# eeZeeProp.net
KiCad netlist of a schematic drawn in EAGLE
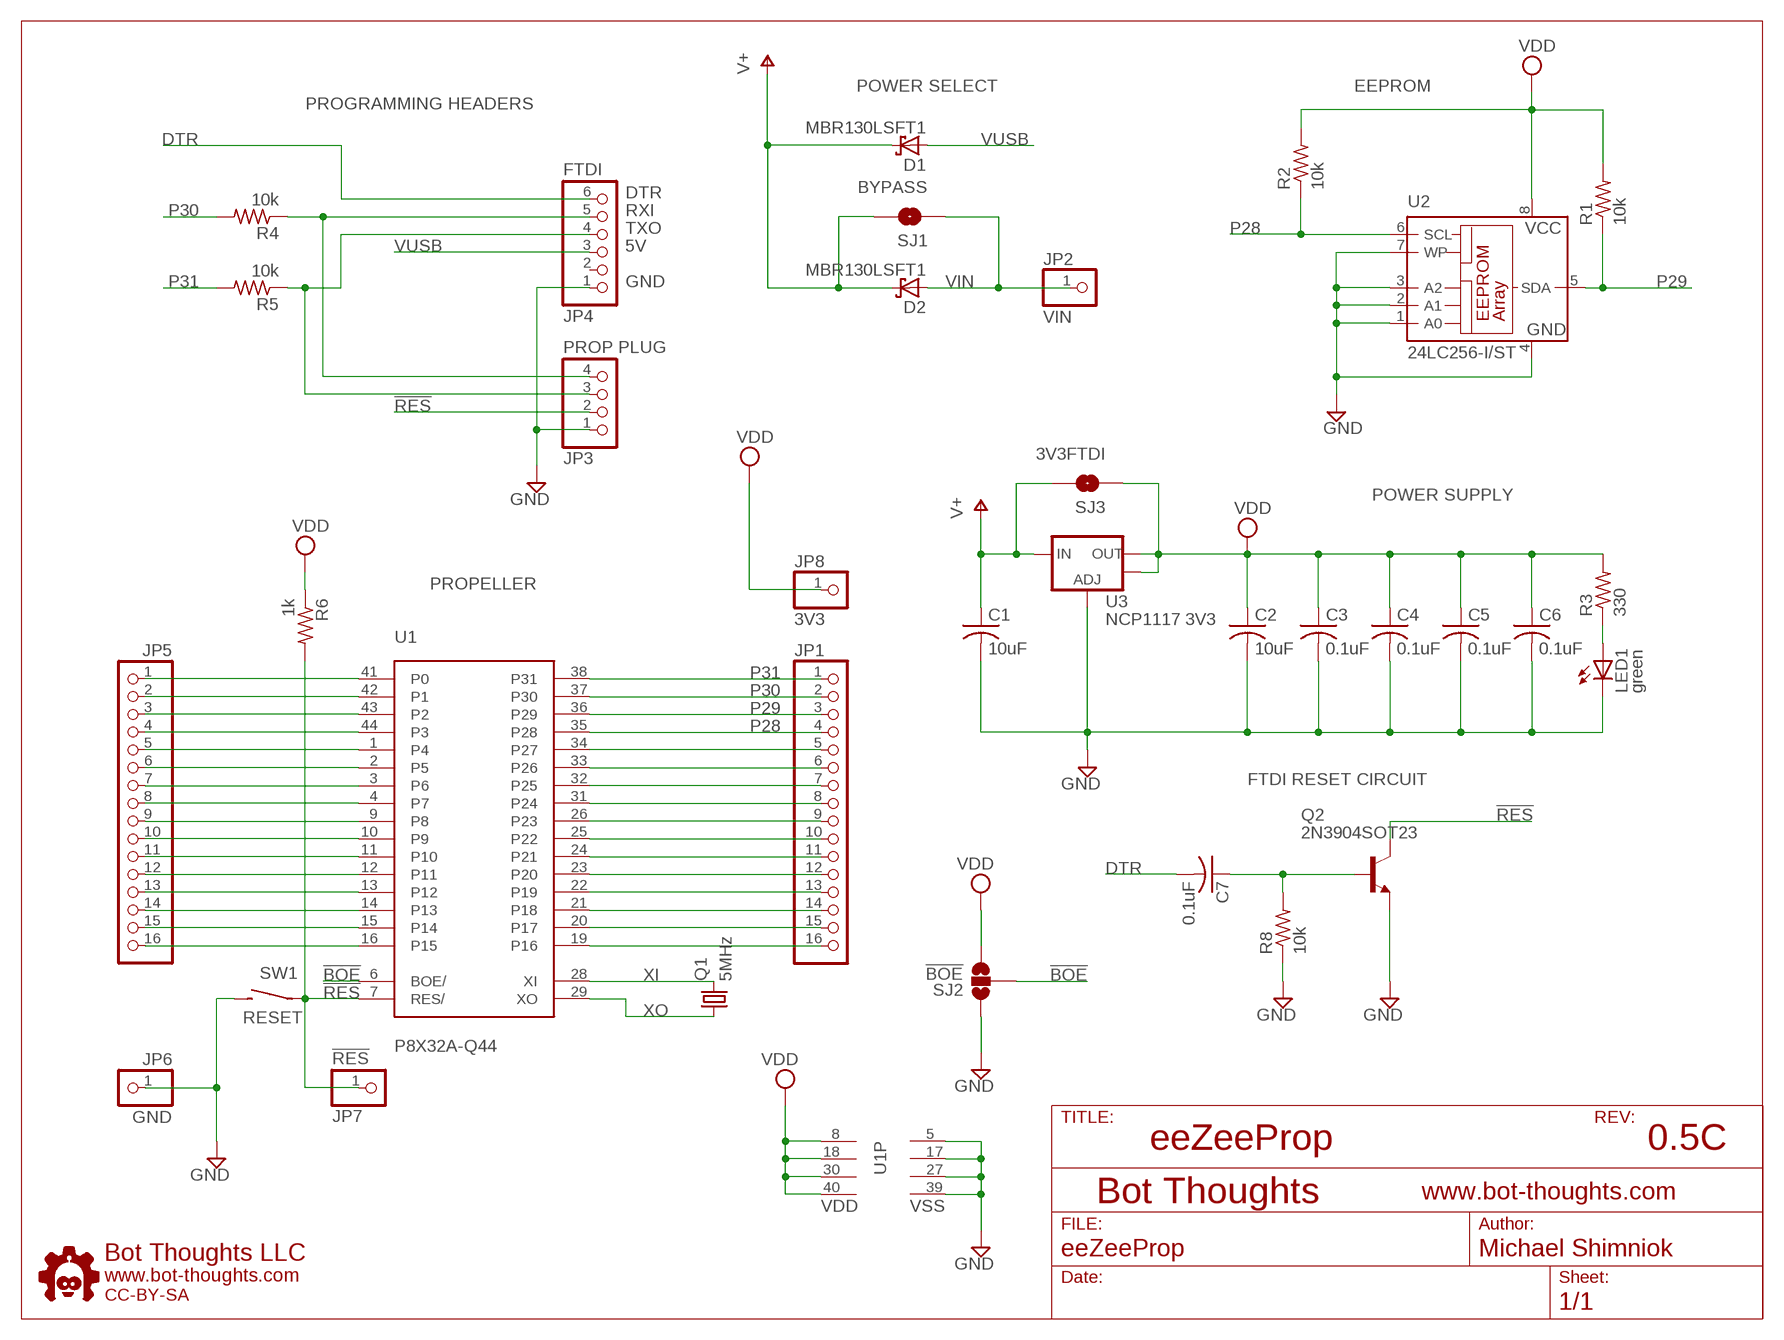
[diagram p0: schematic, sheet 1]

(export (version "E")
  (design (tool "Eeschema 10.0.6"))
  (components
    (comp (ref "C1")
      (value "10uF")
      (footprint "eagle-import:C1206")
      (fields (field (name "PARTNO") "T491A106M006AT"))
      (libsource (lib "eagle-import") (part "C-USC1206"))
    )
    (comp (ref "C2")
      (value "10uF")
      (footprint "eagle-import:C1206")
      (fields (field (name "PARTNO") "T491A106M006AT"))
      (libsource (lib "eagle-import") (part "C-USC1206"))
    )
    (comp (ref "C3")
      (value "0.1uF")
      (footprint "eagle-import:C0603")
      (fields (field (name "PARTNO") "0603YC104KAT2A"))
      (libsource (lib "eagle-import") (part "C-USC0603"))
    )
    (comp (ref "C4")
      (value "0.1uF")
      (footprint "eagle-import:C0603")
      (fields (field (name "PARTNO") "0603YC104KAT2A"))
      (libsource (lib "eagle-import") (part "C-USC0603"))
    )
    (comp (ref "C5")
      (value "0.1uF")
      (footprint "eagle-import:C0603")
      (fields (field (name "PARTNO") "0603YC104KAT2A"))
      (libsource (lib "eagle-import") (part "C-USC0603"))
    )
    (comp (ref "C6")
      (value "0.1uF")
      (footprint "eagle-import:C0603")
      (fields (field (name "PARTNO") "0603YC104KAT2A"))
      (libsource (lib "eagle-import") (part "C-USC0603"))
    )
    (comp (ref "C7")
      (value "0.1uF")
      (footprint "eagle-import:C0603")
      (fields (field (name "PARTNO") "0603YC104KAT2A"))
      (libsource (lib "eagle-import") (part "C-USC0603"))
    )
    (comp (ref "D1")
      (value "MBR130LSFT1")
      (footprint "eagle-import:SOD123FL")
      (fields (field (name "PARTNO") "MBR130LSFT1G"))
      (libsource (lib "eagle-import") (part "SCHOTTKY-DIODE-MBR130LSFT1"))
    )
    (comp (ref "D2")
      (value "MBR130LSFT1")
      (footprint "eagle-import:SOD123FL")
      (fields (field (name "PARTNO") "MBR130LSFT1G"))
      (libsource (lib "eagle-import") (part "SCHOTTKY-DIODE-MBR130LSFT1"))
    )
    (comp (ref "JP1")
      (value "PINHD-1X16_2.54-S")
      (footprint "eagle-import:1X16-S")
      (libsource (lib "eagle-import") (part "PINHD-1X16_2.54-S"))
    )
    (comp (ref "JP2")
      (value "VIN")
      (footprint "eagle-import:1X01")
      (libsource (lib "eagle-import") (part "PINHD-1X01_2.54"))
    )
    (comp (ref "JP3")
      (value "PROP PLUG")
      (footprint "eagle-import:1X04-S")
      (libsource (lib "eagle-import") (part "PINHD-1X04_2.54-S"))
    )
    (comp (ref "JP4")
      (value "FTDI")
      (footprint "eagle-import:1X06-S")
      (fields (field (name "PARTNO") "2211S-06G"))
      (libsource (lib "eagle-import") (part "PINHD-1X06_2.54-S"))
    )
    (comp (ref "JP5")
      (value "PINHD-1X16_2.54-S")
      (footprint "eagle-import:1X16-S")
      (libsource (lib "eagle-import") (part "PINHD-1X16_2.54-S"))
    )
    (comp (ref "JP6")
      (value "GND")
      (footprint "eagle-import:1X01")
      (libsource (lib "eagle-import") (part "PINHD-1X01_2.54"))
    )
    (comp (ref "JP7")
      (value "!RES")
      (footprint "eagle-import:1X01")
      (libsource (lib "eagle-import") (part "PINHD-1X01_2.54"))
    )
    (comp (ref "JP8")
      (value "3V3")
      (footprint "eagle-import:1X01")
      (libsource (lib "eagle-import") (part "PINHD-1X01_2.54"))
    )
    (comp (ref "LED1")
      (value "green")
      (footprint "eagle-import:CHIPLED_1206")
      (fields (field (name "PARTNO") "LG N971-KN-1"))
      (libsource (lib "eagle-import") (part "LEDCHIPLED_1206"))
    )
    (comp (ref "Q1")
      (value "5MHz")
      (footprint "eagle-import:HC49U-V")
      (fields (field (name "OC_FARNELL") "1666969") (field (name "PARTNO") "HC49US-5.000MABJ-UB"))
      (libsource (lib "eagle-import") (part "CRYSTALHC49U-V"))
    )
    (comp (ref "Q2")
      (value "2N3904SOT23")
      (footprint "eagle-import:SOT-23")
      (fields (field (name "PARTNO") "MMBT3904LT3G"))
      (libsource (lib "eagle-import") (part "2N3904SOT23"))
    )
    (comp (ref "R1")
      (value "10k")
      (footprint "eagle-import:R0603")
      (fields (field (name "PARTNO") "ERJ-3GEYJ103V"))
      (libsource (lib "eagle-import") (part "R-US_R0603"))
    )
    (comp (ref "R2")
      (value "10k")
      (footprint "eagle-import:R0603")
      (fields (field (name "PARTNO") "ERJ-3GEYJ103V"))
      (libsource (lib "eagle-import") (part "R-US_R0603"))
    )
    (comp (ref "R3")
      (value "330")
      (footprint "eagle-import:R0603")
      (fields (field (name "PARTNO") "ERJ-3GEYJ331V"))
      (libsource (lib "eagle-import") (part "R-US_R0603"))
    )
    (comp (ref "R4")
      (value "10k")
      (footprint "eagle-import:R0603")
      (fields (field (name "PARTNO") "RC0603JR-071KL"))
      (libsource (lib "eagle-import") (part "R-US_R0603"))
    )
    (comp (ref "R5")
      (value "10k")
      (footprint "eagle-import:R0603")
      (fields (field (name "PARTNO") "RC0603JR-071KL"))
      (libsource (lib "eagle-import") (part "R-US_R0603"))
    )
    (comp (ref "R6")
      (value "1k")
      (footprint "eagle-import:R0603")
      (fields (field (name "PARTNO") "RC0603JR-071KL"))
      (libsource (lib "eagle-import") (part "R-US_R0603"))
    )
    (comp (ref "R8")
      (value "10k")
      (footprint "eagle-import:R0603")
      (fields (field (name "PARTNO") "ERJ-3GEYJ103V"))
      (libsource (lib "eagle-import") (part "R-US_R0603"))
    )
    (comp (ref "SJ1")
      (value "BYPASS")
      (footprint "eagle-import:SJ_2S-NO")
      (libsource (lib "eagle-import") (part "SOLDERJUMPERNO"))
    )
    (comp (ref "SJ2")
      (value "!BOE")
      (footprint "eagle-import:SJ_3")
      (libsource (lib "eagle-import") (part "SOLDERJUMPER_2WAYS"))
    )
    (comp (ref "SJ3")
      (value "3V3FTDI")
      (footprint "eagle-import:SJ_2S-NO")
      (libsource (lib "eagle-import") (part "SOLDERJUMPERNO"))
    )
    (comp (ref "SW1")
      (value "RESET")
      (footprint "eagle-import:6MMTACTILE_RECT")
      (fields (field (name "PARTNO") "MJTP1243"))
      (libsource (lib "eagle-import") (part "SPST_TAC_RECT1"))
    )
    (comp (ref "U$1")
      (value "BTLOGO-LOGO-MD")
      (footprint "eagle-import:BTLOGOM")
      (libsource (lib "eagle-import") (part "BTLOGO-LOGO-MD"))
    )
    (comp (ref "U1")
      (value "P8X32A-Q44")
      (footprint "eagle-import:P8X32A-Q44")
      (fields (field (name "PARTNO") "P8X32A-Q44"))
      (libsource (lib "eagle-import") (part "P8X32A-Q44"))
    )
    (comp (ref "U2")
      (value "24LC256-I/ST")
      (footprint "eagle-import:SO-08")
      (fields
        (field (name "MF") "MICROCHIP")
        (field (name "MPN") "24LC128-I/SNG")
        (field (name "MF_1") "OnSemi")
        (field (name "MPN_1") "CAT24C256WI-GT3")
        (field (name "PARTNO") "CAT24C256WI-GT3")
      )
      (libsource (lib "eagle-import") (part "24SNLC128"))
    )
    (comp (ref "U3")
      (value "NCP1117 3V3")
      (footprint "eagle-import:SOT223")
      (fields (field (name "PARTNO") "NCP1117ST33T3G"))
      (libsource (lib "eagle-import") (part "V_REG_LM1117SOT223"))
    )
  )
  (nets
    (net (code "1") (name "/DTR") (class "Default")
      (node (ref "C7") (pin "2") (pinfunction "2_2") (pintype "passive"))
      (node (ref "JP4") (pin "6") (pinfunction "6_6") (pintype "passive"))
    )
    (net (code "2") (name "/P28") (class "Default")
      (node (ref "JP1") (pin "4") (pinfunction "4_4") (pintype "passive"))
      (node (ref "R2") (pin "1") (pinfunction "1_1") (pintype "passive"))
      (node (ref "U1") (pin "35") (pinfunction "P28_35") (pintype "bidirectional"))
      (node (ref "U2") (pin "6") (pinfunction "SCL_6") (pintype "input"))
    )
    (net (code "3") (name "/P29") (class "Default")
      (node (ref "JP1") (pin "3") (pinfunction "3_3") (pintype "passive"))
      (node (ref "R1") (pin "1") (pinfunction "1_1") (pintype "passive"))
      (node (ref "U1") (pin "36") (pinfunction "P29_36") (pintype "bidirectional"))
      (node (ref "U2") (pin "5") (pinfunction "SDA_5") (pintype "bidirectional"))
    )
    (net (code "4") (name "/P30") (class "Default")
      (node (ref "JP1") (pin "2") (pinfunction "2_2") (pintype "passive"))
      (node (ref "R4") (pin "2") (pinfunction "2_2") (pintype "passive"))
      (node (ref "U1") (pin "37") (pinfunction "P30_37") (pintype "bidirectional"))
    )
    (net (code "5") (name "/P31") (class "Default")
      (node (ref "JP1") (pin "1") (pinfunction "1_1") (pintype "passive"))
      (node (ref "R5") (pin "2") (pinfunction "2_2") (pintype "passive"))
      (node (ref "U1") (pin "38") (pinfunction "P31_38") (pintype "bidirectional"))
    )
    (net (code "6") (name "/VIN") (class "Default")
      (node (ref "D2") (pin "A") (pinfunction "A_A") (pintype "passive"))
      (node (ref "JP2") (pin "1") (pinfunction "1_1") (pintype "passive"))
      (node (ref "SJ1") (pin "1") (pinfunction "1_1") (pintype "passive"))
    )
    (net (code "7") (name "/VUSB") (class "Default")
      (node (ref "D1") (pin "A") (pinfunction "A_A") (pintype "passive"))
      (node (ref "JP4") (pin "3") (pinfunction "3_3") (pintype "passive"))
    )
    (net (code "8") (name "/XI") (class "Default")
      (node (ref "Q1") (pin "2") (pinfunction "2_2") (pintype "passive"))
      (node (ref "U1") (pin "28") (pinfunction "XI_28") (pintype "input"))
    )
    (net (code "9") (name "/XO") (class "Default")
      (node (ref "Q1") (pin "1") (pinfunction "1_1") (pintype "passive"))
      (node (ref "U1") (pin "29") (pinfunction "XO_29") (pintype "output"))
    )
    (net (code "10") (name "/~{BOE}") (class "Default")
      (node (ref "SJ2") (pin "2") (pinfunction "2_2") (pintype "passive"))
      (node (ref "U1") (pin "6") (pinfunction "BOE/_6") (pintype "input"))
    )
    (net (code "11") (name "/~{RES}") (class "Default")
      (node (ref "JP3") (pin "2") (pinfunction "2_2") (pintype "passive"))
      (node (ref "JP7") (pin "1") (pinfunction "1_1") (pintype "passive"))
      (node (ref "Q2") (pin "1") (pinfunction "C_1") (pintype "passive"))
      (node (ref "R6") (pin "2") (pinfunction "2_2") (pintype "passive"))
      (node (ref "SW1") (pin "P$1") (pinfunction "P_P$1") (pintype "passive"))
      (node (ref "U1") (pin "7") (pinfunction "RES/_7") (pintype "bidirectional"))
    )
    (net (code "12") (name "GND") (class "Default")
      (node (ref "C1") (pin "2") (pinfunction "2_2") (pintype "passive"))
      (node (ref "C2") (pin "2") (pinfunction "2_2") (pintype "passive"))
      (node (ref "C3") (pin "2") (pinfunction "2_2") (pintype "passive"))
      (node (ref "C4") (pin "2") (pinfunction "2_2") (pintype "passive"))
      (node (ref "C5") (pin "2") (pinfunction "2_2") (pintype "passive"))
      (node (ref "C6") (pin "2") (pinfunction "2_2") (pintype "passive"))
      (node (ref "JP3") (pin "1") (pinfunction "1_1") (pintype "passive"))
      (node (ref "JP4") (pin "1") (pinfunction "1_1") (pintype "passive"))
      (node (ref "JP6") (pin "1") (pinfunction "1_1") (pintype "passive"))
      (node (ref "LED1") (pin "C") (pinfunction "C_C") (pintype "passive"))
      (node (ref "Q2") (pin "2") (pinfunction "E_2") (pintype "passive"))
      (node (ref "R8") (pin "1") (pinfunction "1_1") (pintype "passive"))
      (node (ref "SJ2") (pin "1") (pinfunction "1_1") (pintype "passive"))
      (node (ref "SW1") (pin "P$2") (pinfunction "S_P$2") (pintype "passive"))
      (node (ref "U1") (pin "17") (pinfunction "VSS_17") (pintype "power_in"))
      (node (ref "U1") (pin "27") (pinfunction "VSS_27") (pintype "power_in"))
      (node (ref "U1") (pin "39") (pinfunction "VSS_39") (pintype "power_in"))
      (node (ref "U1") (pin "5") (pinfunction "VSS_5") (pintype "power_in"))
      (node (ref "U2") (pin "1") (pinfunction "A0_1") (pintype "input"))
      (node (ref "U2") (pin "2") (pinfunction "A1_2") (pintype "input"))
      (node (ref "U2") (pin "3") (pinfunction "A2_3") (pintype "input"))
      (node (ref "U2") (pin "4") (pinfunction "GND_4") (pintype "power_in"))
      (node (ref "U2") (pin "7") (pinfunction "WP_7") (pintype "input"))
      (node (ref "U3") (pin "1") (pinfunction "ADJ_1") (pintype "input"))
    )
    (net (code "13") (name "Net-(JP3-Pad3)") (class "Default")
      (node (ref "JP3") (pin "3") (pinfunction "3_3") (pintype "passive"))
      (node (ref "JP4") (pin "4") (pinfunction "4_4") (pintype "passive"))
      (node (ref "R5") (pin "1") (pinfunction "1_1") (pintype "passive"))
    )
    (net (code "14") (name "Net-(JP3-Pad4)") (class "Default")
      (node (ref "JP3") (pin "4") (pinfunction "4_4") (pintype "passive"))
      (node (ref "JP4") (pin "5") (pinfunction "5_5") (pintype "passive"))
      (node (ref "R4") (pin "1") (pinfunction "1_1") (pintype "passive"))
    )
    (net (code "15") (name "Net-(LED1-PadA)") (class "Default")
      (node (ref "LED1") (pin "A") (pinfunction "A_A") (pintype "passive"))
      (node (ref "R3") (pin "1") (pinfunction "1_1") (pintype "passive"))
    )
    (net (code "16") (name "Net-(Q2-B)") (class "Default")
      (node (ref "C7") (pin "1") (pinfunction "1_1") (pintype "passive"))
      (node (ref "Q2") (pin "3") (pinfunction "B_3") (pintype "passive"))
      (node (ref "R8") (pin "2") (pinfunction "2_2") (pintype "passive"))
    )
    (net (code "17") (name "Net-(U1B-P0)") (class "Default")
      (node (ref "JP5") (pin "1") (pinfunction "1_1") (pintype "passive"))
      (node (ref "U1") (pin "41") (pinfunction "P0_41") (pintype "bidirectional"))
    )
    (net (code "18") (name "Net-(U1B-P1)") (class "Default")
      (node (ref "JP5") (pin "2") (pinfunction "2_2") (pintype "passive"))
      (node (ref "U1") (pin "42") (pinfunction "P1_42") (pintype "bidirectional"))
    )
    (net (code "19") (name "Net-(U1B-P2)") (class "Default")
      (node (ref "JP5") (pin "3") (pinfunction "3_3") (pintype "passive"))
      (node (ref "U1") (pin "43") (pinfunction "P2_43") (pintype "bidirectional"))
    )
    (net (code "20") (name "Net-(U1B-P3)") (class "Default")
      (node (ref "JP5") (pin "4") (pinfunction "4_4") (pintype "passive"))
      (node (ref "U1") (pin "44") (pinfunction "P3_44") (pintype "bidirectional"))
    )
    (net (code "21") (name "Net-(U1B-P4)") (class "Default")
      (node (ref "JP5") (pin "5") (pinfunction "5_5") (pintype "passive"))
      (node (ref "U1") (pin "1") (pinfunction "P4_1") (pintype "bidirectional"))
    )
    (net (code "22") (name "Net-(U1B-P5)") (class "Default")
      (node (ref "JP5") (pin "6") (pinfunction "6_6") (pintype "passive"))
      (node (ref "U1") (pin "2") (pinfunction "P5_2") (pintype "bidirectional"))
    )
    (net (code "23") (name "Net-(U1B-P6)") (class "Default")
      (node (ref "JP5") (pin "7") (pinfunction "7_7") (pintype "passive"))
      (node (ref "U1") (pin "3") (pinfunction "P6_3") (pintype "bidirectional"))
    )
    (net (code "24") (name "Net-(U1B-P7)") (class "Default")
      (node (ref "JP5") (pin "8") (pinfunction "8_8") (pintype "passive"))
      (node (ref "U1") (pin "4") (pinfunction "P7_4") (pintype "bidirectional"))
    )
    (net (code "25") (name "Net-(U1B-P8)") (class "Default")
      (node (ref "JP5") (pin "9") (pinfunction "9_9") (pintype "passive"))
      (node (ref "U1") (pin "9") (pinfunction "P8_9") (pintype "bidirectional"))
    )
    (net (code "26") (name "Net-(U1B-P9)") (class "Default")
      (node (ref "JP5") (pin "10") (pinfunction "10_10") (pintype "passive"))
      (node (ref "U1") (pin "10") (pinfunction "P9_10") (pintype "bidirectional"))
    )
    (net (code "27") (name "Net-(U1B-P10)") (class "Default")
      (node (ref "JP5") (pin "11") (pinfunction "11_11") (pintype "passive"))
      (node (ref "U1") (pin "11") (pinfunction "P10_11") (pintype "bidirectional"))
    )
    (net (code "28") (name "Net-(U1B-P11)") (class "Default")
      (node (ref "JP5") (pin "12") (pinfunction "12_12") (pintype "passive"))
      (node (ref "U1") (pin "12") (pinfunction "P11_12") (pintype "bidirectional"))
    )
    (net (code "29") (name "Net-(U1B-P12)") (class "Default")
      (node (ref "JP5") (pin "13") (pinfunction "13_13") (pintype "passive"))
      (node (ref "U1") (pin "13") (pinfunction "P12_13") (pintype "bidirectional"))
    )
    (net (code "30") (name "Net-(U1B-P13)") (class "Default")
      (node (ref "JP5") (pin "14") (pinfunction "14_14") (pintype "passive"))
      (node (ref "U1") (pin "14") (pinfunction "P13_14") (pintype "bidirectional"))
    )
    (net (code "31") (name "Net-(U1B-P14)") (class "Default")
      (node (ref "JP5") (pin "15") (pinfunction "15_15") (pintype "passive"))
      (node (ref "U1") (pin "15") (pinfunction "P14_15") (pintype "bidirectional"))
    )
    (net (code "32") (name "Net-(U1B-P15)") (class "Default")
      (node (ref "JP5") (pin "16") (pinfunction "16_16") (pintype "passive"))
      (node (ref "U1") (pin "16") (pinfunction "P15_16") (pintype "bidirectional"))
    )
    (net (code "33") (name "Net-(U1B-P16)") (class "Default")
      (node (ref "JP1") (pin "16") (pinfunction "16_16") (pintype "passive"))
      (node (ref "U1") (pin "19") (pinfunction "P16_19") (pintype "bidirectional"))
    )
    (net (code "34") (name "Net-(U1B-P17)") (class "Default")
      (node (ref "JP1") (pin "15") (pinfunction "15_15") (pintype "passive"))
      (node (ref "U1") (pin "20") (pinfunction "P17_20") (pintype "bidirectional"))
    )
    (net (code "35") (name "Net-(U1B-P18)") (class "Default")
      (node (ref "JP1") (pin "14") (pinfunction "14_14") (pintype "passive"))
      (node (ref "U1") (pin "21") (pinfunction "P18_21") (pintype "bidirectional"))
    )
    (net (code "36") (name "Net-(U1B-P19)") (class "Default")
      (node (ref "JP1") (pin "13") (pinfunction "13_13") (pintype "passive"))
      (node (ref "U1") (pin "22") (pinfunction "P19_22") (pintype "bidirectional"))
    )
    (net (code "37") (name "Net-(U1B-P20)") (class "Default")
      (node (ref "JP1") (pin "12") (pinfunction "12_12") (pintype "passive"))
      (node (ref "U1") (pin "23") (pinfunction "P20_23") (pintype "bidirectional"))
    )
    (net (code "38") (name "Net-(U1B-P21)") (class "Default")
      (node (ref "JP1") (pin "11") (pinfunction "11_11") (pintype "passive"))
      (node (ref "U1") (pin "24") (pinfunction "P21_24") (pintype "bidirectional"))
    )
    (net (code "39") (name "Net-(U1B-P22)") (class "Default")
      (node (ref "JP1") (pin "10") (pinfunction "10_10") (pintype "passive"))
      (node (ref "U1") (pin "25") (pinfunction "P22_25") (pintype "bidirectional"))
    )
    (net (code "40") (name "Net-(U1B-P23)") (class "Default")
      (node (ref "JP1") (pin "9") (pinfunction "9_9") (pintype "passive"))
      (node (ref "U1") (pin "26") (pinfunction "P23_26") (pintype "bidirectional"))
    )
    (net (code "41") (name "Net-(U1B-P24)") (class "Default")
      (node (ref "JP1") (pin "8") (pinfunction "8_8") (pintype "passive"))
      (node (ref "U1") (pin "31") (pinfunction "P24_31") (pintype "bidirectional"))
    )
    (net (code "42") (name "Net-(U1B-P25)") (class "Default")
      (node (ref "JP1") (pin "7") (pinfunction "7_7") (pintype "passive"))
      (node (ref "U1") (pin "32") (pinfunction "P25_32") (pintype "bidirectional"))
    )
    (net (code "43") (name "Net-(U1B-P26)") (class "Default")
      (node (ref "JP1") (pin "6") (pinfunction "6_6") (pintype "passive"))
      (node (ref "U1") (pin "33") (pinfunction "P26_33") (pintype "bidirectional"))
    )
    (net (code "44") (name "Net-(U1B-P27)") (class "Default")
      (node (ref "JP1") (pin "5") (pinfunction "5_5") (pintype "passive"))
      (node (ref "U1") (pin "34") (pinfunction "P27_34") (pintype "bidirectional"))
    )
    (net (code "45") (name "V+") (class "Default")
      (node (ref "C1") (pin "1") (pinfunction "1_1") (pintype "passive"))
      (node (ref "D1") (pin "C") (pinfunction "C_C") (pintype "passive"))
      (node (ref "D2") (pin "C") (pinfunction "C_C") (pintype "passive"))
      (node (ref "SJ1") (pin "2") (pinfunction "2_2") (pintype "passive"))
      (node (ref "SJ3") (pin "2") (pinfunction "2_2") (pintype "passive"))
      (node (ref "U3") (pin "3") (pinfunction "IN_3") (pintype "input"))
    )
    (net (code "46") (name "VDD") (class "Default")
      (node (ref "C2") (pin "1") (pinfunction "1_1") (pintype "passive"))
      (node (ref "C3") (pin "1") (pinfunction "1_1") (pintype "passive"))
      (node (ref "C4") (pin "1") (pinfunction "1_1") (pintype "passive"))
      (node (ref "C5") (pin "1") (pinfunction "1_1") (pintype "passive"))
      (node (ref "C6") (pin "1") (pinfunction "1_1") (pintype "passive"))
      (node (ref "JP8") (pin "1") (pinfunction "1_1") (pintype "passive"))
      (node (ref "R1") (pin "2") (pinfunction "2_2") (pintype "passive"))
      (node (ref "R2") (pin "2") (pinfunction "2_2") (pintype "passive"))
      (node (ref "R3") (pin "2") (pinfunction "2_2") (pintype "passive"))
      (node (ref "R6") (pin "1") (pinfunction "1_1") (pintype "passive"))
      (node (ref "SJ2") (pin "3") (pinfunction "3_3") (pintype "passive"))
      (node (ref "SJ3") (pin "1") (pinfunction "1_1") (pintype "passive"))
      (node (ref "U1") (pin "18") (pinfunction "VDD_18") (pintype "power_in"))
      (node (ref "U1") (pin "30") (pinfunction "VDD_30") (pintype "power_in"))
      (node (ref "U1") (pin "40") (pinfunction "VDD_40") (pintype "power_in"))
      (node (ref "U1") (pin "8") (pinfunction "VDD_8") (pintype "power_in"))
      (node (ref "U2") (pin "8") (pinfunction "VCC_8") (pintype "power_in"))
      (node (ref "U3") (pin "2") (pinfunction "OUT_2") (pintype "output"))
      (node (ref "U3") (pin "4") (pinfunction "OUT_4") (pintype "output"))
    )
    (net (code "47") (name "unconnected-(JP4-Pad2)") (class "Default")
      (node (ref "JP4") (pin "2") (pinfunction "2_2") (pintype "passive"))
    )
  )
)
